# untitled.net
KiCad netlist of a schematic drawn in EAGLE
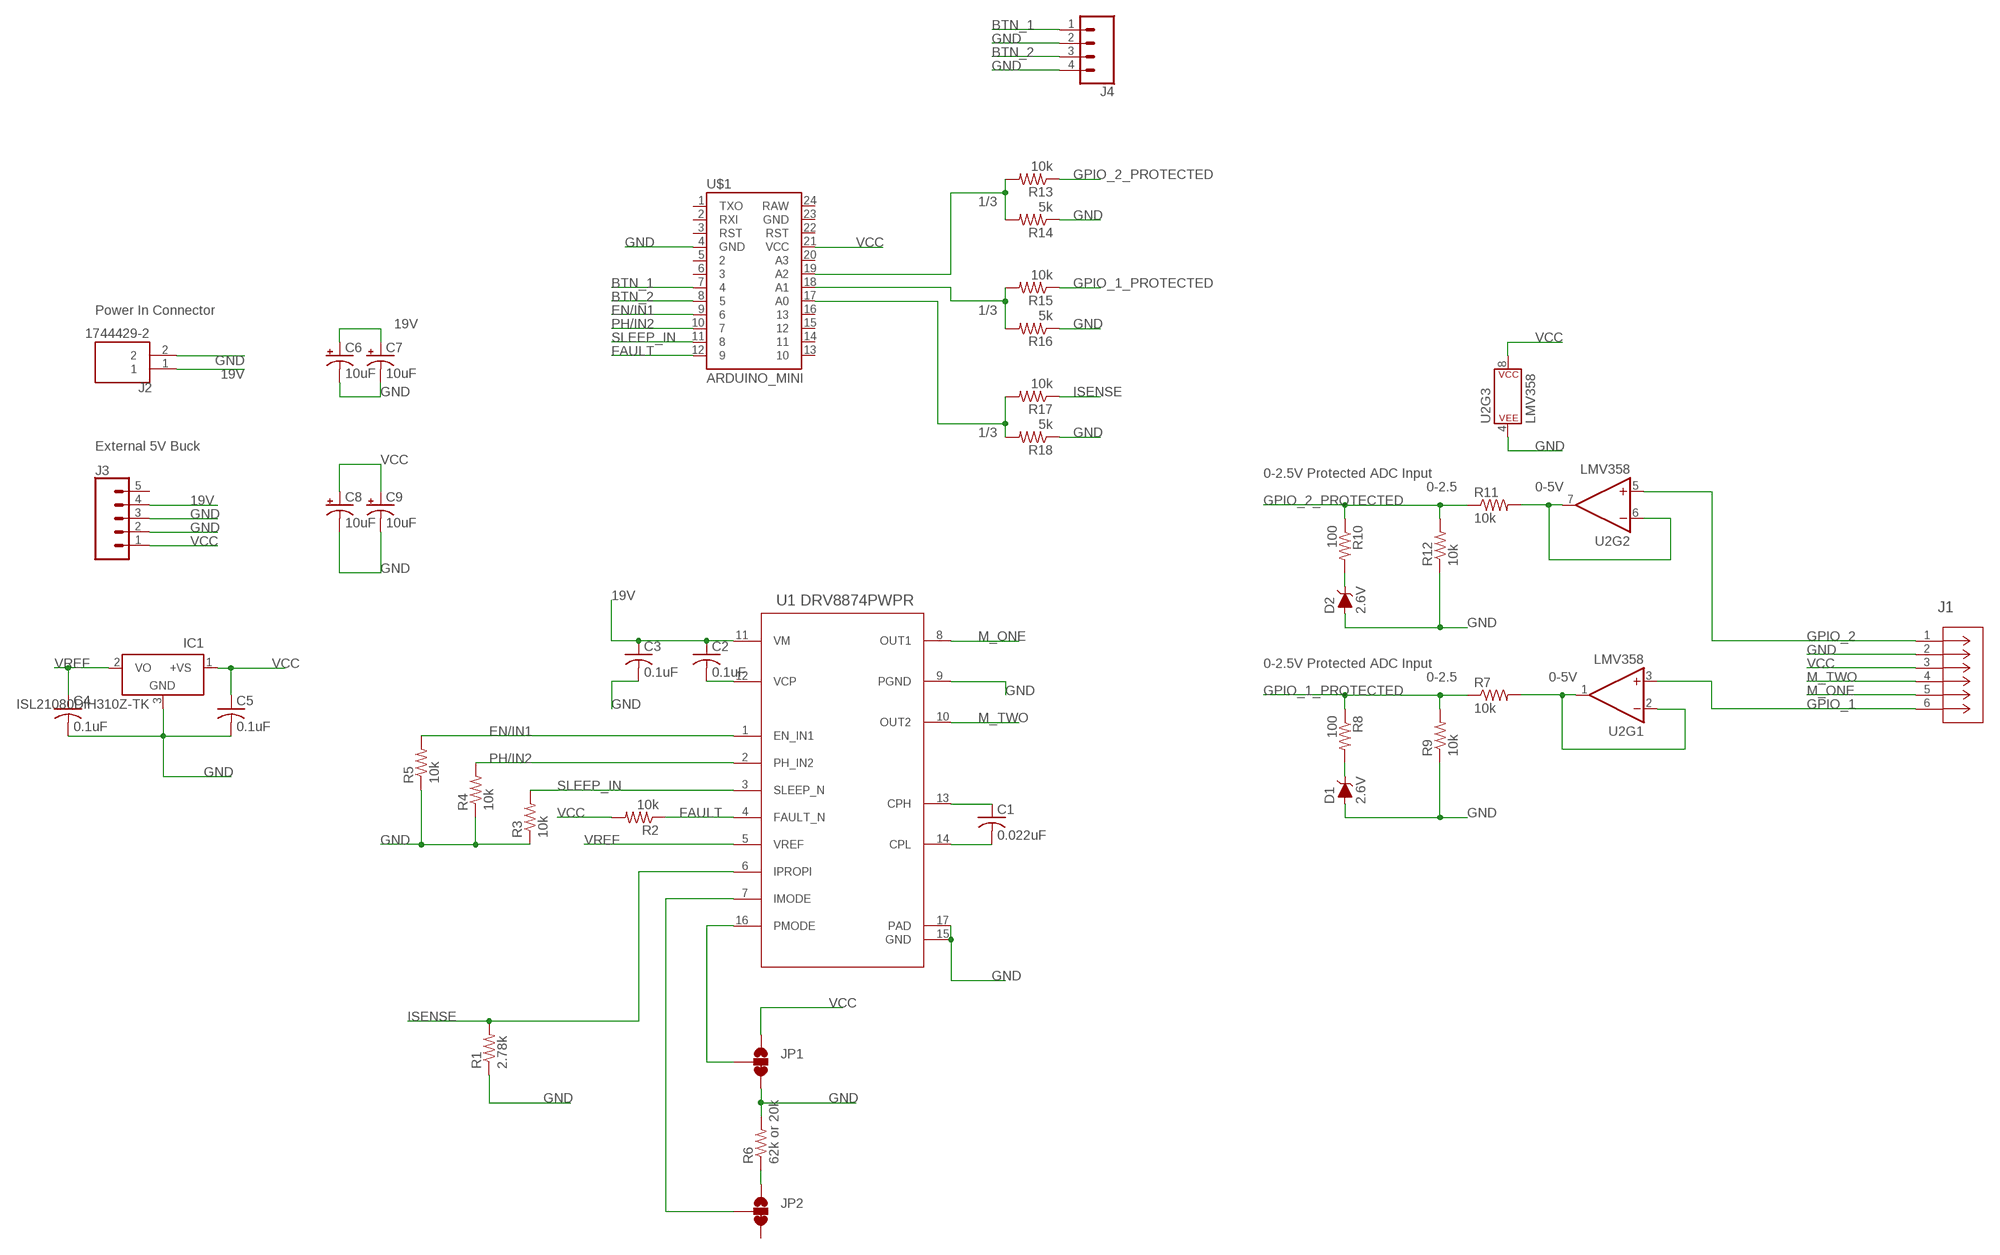
[diagram p0: schematic, sheet 1]

(export (version "E")
  (design (tool "Eeschema 10.0.6"))
  (components
    (comp (ref "C1")
      (value "0.022uF")
      (footprint "eagle-import:C0805K")
      (libsource (lib "eagle-import") (part "C-USC0805K"))
    )
    (comp (ref "C2")
      (value "0.1uF")
      (footprint "eagle-import:C0805K")
      (libsource (lib "eagle-import") (part "C-USC0805K"))
    )
    (comp (ref "C3")
      (value "0.1uF")
      (footprint "eagle-import:C0805K")
      (libsource (lib "eagle-import") (part "C-USC0805K"))
    )
    (comp (ref "C4")
      (value "0.1uF")
      (footprint "eagle-import:C0805K")
      (libsource (lib "eagle-import") (part "C-USC0805K"))
    )
    (comp (ref "C5")
      (value "0.1uF")
      (footprint "eagle-import:C0805K")
      (libsource (lib "eagle-import") (part "C-USC0805K"))
    )
    (comp (ref "C6")
      (value "10uF")
      (footprint "eagle-import:E2,5-6")
      (libsource (lib "eagle-import") (part "CPOL-USE2.5-6"))
    )
    (comp (ref "C7")
      (value "10uF")
      (footprint "eagle-import:E2,5-6")
      (libsource (lib "eagle-import") (part "CPOL-USE2.5-6"))
    )
    (comp (ref "C8")
      (value "10uF")
      (footprint "eagle-import:E2,5-6")
      (libsource (lib "eagle-import") (part "CPOL-USE2.5-6"))
    )
    (comp (ref "C9")
      (value "10uF")
      (footprint "eagle-import:E2,5-6")
      (libsource (lib "eagle-import") (part "CPOL-USE2.5-6"))
    )
    (comp (ref "D1")
      (value "2.6V")
      (footprint "eagle-import:SOD-323")
      (libsource (lib "eagle-import") (part "DIODE-ZENER-BZT52C3V6S"))
    )
    (comp (ref "D2")
      (value "2.6V")
      (footprint "eagle-import:SOD-323")
      (libsource (lib "eagle-import") (part "DIODE-ZENER-BZT52C3V6S"))
    )
    (comp (ref "IC1")
      (value "ISL21080DIH310Z-TK")
      (footprint "eagle-import:SOT23")
      (libsource (lib "eagle-import") (part "LM50"))
    )
    (comp (ref "J1")
      (value "39301060")
      (footprint "eagle-import:CON_39301060")
      (fields (field (name "COPYRIGHT") "Copyright (C) 2022 Ultra Librarian. All rights reserved."))
      (libsource (lib "eagle-import") (part "39301060"))
    )
    (comp (ref "J2")
      (value "1744429-2")
      (footprint "eagle-import:TE_1744429-2")
      (fields (field (name "MANUFACTURER") "TE"))
      (libsource (lib "eagle-import") (part "1744429-2"))
    )
    (comp (ref "J3")
      (value "CONN_05")
      (footprint "eagle-import:1X05")
      (libsource (lib "eagle-import") (part "CONN_05"))
    )
    (comp (ref "J4")
      (value "CONN_041X04_NO_SILK")
      (footprint "eagle-import:1X04_NO_SILK")
      (libsource (lib "eagle-import") (part "CONN_041X04_NO_SILK"))
    )
    (comp (ref "JP1")
      (value "JUMPER-SMT_3_1-NC_TRACE_SILK")
      (footprint "eagle-import:SMT-JUMPER_3_1-NC_TRACE_SILK")
      (libsource (lib "eagle-import") (part "JUMPER-SMT_3_1-NC_TRACE_SILK"))
    )
    (comp (ref "JP2")
      (value "JUMPER-SMT_3_1-NC_TRACE_SILK")
      (footprint "eagle-import:SMT-JUMPER_3_1-NC_TRACE_SILK")
      (libsource (lib "eagle-import") (part "JUMPER-SMT_3_1-NC_TRACE_SILK"))
    )
    (comp (ref "R1")
      (value "2.78k")
      (footprint "eagle-import:R0805")
      (libsource (lib "eagle-import") (part "R-US_R0805"))
    )
    (comp (ref "R2")
      (value "10k")
      (footprint "eagle-import:R0805")
      (libsource (lib "eagle-import") (part "R-US_R0805"))
    )
    (comp (ref "R3")
      (value "10k")
      (footprint "eagle-import:R0805")
      (libsource (lib "eagle-import") (part "R-US_R0805"))
    )
    (comp (ref "R4")
      (value "10k")
      (footprint "eagle-import:R0805")
      (libsource (lib "eagle-import") (part "R-US_R0805"))
    )
    (comp (ref "R5")
      (value "10k")
      (footprint "eagle-import:R0805")
      (libsource (lib "eagle-import") (part "R-US_R0805"))
    )
    (comp (ref "R6")
      (value "62k or 20k")
      (footprint "eagle-import:R0805")
      (libsource (lib "eagle-import") (part "R-US_R0805"))
    )
    (comp (ref "R7")
      (value "10k")
      (footprint "eagle-import:R0805")
      (libsource (lib "eagle-import") (part "R-US_R0805"))
    )
    (comp (ref "R8")
      (value "100")
      (footprint "eagle-import:R0805")
      (libsource (lib "eagle-import") (part "R-US_R0805"))
    )
    (comp (ref "R9")
      (value "10k")
      (footprint "eagle-import:R0805")
      (libsource (lib "eagle-import") (part "R-US_R0805"))
    )
    (comp (ref "R10")
      (value "100")
      (footprint "eagle-import:R0805")
      (libsource (lib "eagle-import") (part "R-US_R0805"))
    )
    (comp (ref "R11")
      (value "10k")
      (footprint "eagle-import:R0805")
      (libsource (lib "eagle-import") (part "R-US_R0805"))
    )
    (comp (ref "R12")
      (value "10k")
      (footprint "eagle-import:R0805")
      (libsource (lib "eagle-import") (part "R-US_R0805"))
    )
    (comp (ref "R13")
      (value "10k")
      (footprint "eagle-import:R0805")
      (libsource (lib "eagle-import") (part "R-US_R0805"))
    )
    (comp (ref "R14")
      (value "5k")
      (footprint "eagle-import:R0805")
      (libsource (lib "eagle-import") (part "R-US_R0805"))
    )
    (comp (ref "R15")
      (value "10k")
      (footprint "eagle-import:R0805")
      (libsource (lib "eagle-import") (part "R-US_R0805"))
    )
    (comp (ref "R16")
      (value "5k")
      (footprint "eagle-import:R0805")
      (libsource (lib "eagle-import") (part "R-US_R0805"))
    )
    (comp (ref "R17")
      (value "10k")
      (footprint "eagle-import:R0805")
      (libsource (lib "eagle-import") (part "R-US_R0805"))
    )
    (comp (ref "R18")
      (value "5k")
      (footprint "eagle-import:R0805")
      (libsource (lib "eagle-import") (part "R-US_R0805"))
    )
    (comp (ref "U$1")
      (value "ARDUINO_MINI")
      (footprint "eagle-import:ARDUINO_MINI")
      (libsource (lib "eagle-import") (part "ARDUINO_MINI"))
    )
    (comp (ref "U1")
      (value "DRV8874PWPR")
      (footprint "eagle-import:PWP0016J_N")
      (fields (field (name "COPYRIGHT") "Copyright (C) 2022 Ultra Librarian. All rights reserved."))
      (libsource (lib "eagle-import") (part "DRV8874PWPR"))
    )
    (comp (ref "U2")
      (value "LMV358")
      (footprint "eagle-import:SO08")
      (libsource (lib "eagle-import") (part "LMV358SOIC"))
    )
  )
  (nets
    (net (code "1") (name "/19V") (class "Default")
      (node (ref "C2") (pin "1") (pinfunction "1_1") (pintype "passive"))
      (node (ref "C3") (pin "1") (pinfunction "1_1") (pintype "passive"))
      (node (ref "C6") (pin "+") (pinfunction "+_+") (pintype "passive"))
      (node (ref "C7") (pin "+") (pinfunction "+_+") (pintype "passive"))
      (node (ref "J2") (pin "1") (pinfunction "1_1") (pintype "passive"))
      (node (ref "J3") (pin "4") (pinfunction "4_4") (pintype "passive"))
      (node (ref "U1") (pin "11") (pinfunction "VM_11") (pintype "power_in"))
    )
    (net (code "2") (name "/BTN_1") (class "Default")
      (node (ref "J4") (pin "1") (pinfunction "1_1") (pintype "passive"))
      (node (ref "U$1") (pin "7") (pinfunction "4_7") (pintype "bidirectional"))
    )
    (net (code "3") (name "/BTN_2") (class "Default")
      (node (ref "J4") (pin "3") (pinfunction "3_3") (pintype "passive"))
      (node (ref "U$1") (pin "8") (pinfunction "5_8") (pintype "bidirectional"))
    )
    (net (code "4") (name "/EN{slash}IN1") (class "Default")
      (node (ref "R5") (pin "2") (pinfunction "2_2") (pintype "passive"))
      (node (ref "U$1") (pin "9") (pinfunction "6_9") (pintype "bidirectional"))
      (node (ref "U1") (pin "1") (pinfunction "EN_IN1_1") (pintype "input"))
    )
    (net (code "5") (name "/FAULT") (class "Default")
      (node (ref "R2") (pin "1") (pinfunction "1_1") (pintype "passive"))
      (node (ref "U$1") (pin "12") (pinfunction "9_12") (pintype "bidirectional"))
      (node (ref "U1") (pin "4") (pinfunction "FAULT_N_4") (pintype "open_collector"))
    )
    (net (code "6") (name "/GND") (class "Default")
      (node (ref "C3") (pin "2") (pinfunction "2_2") (pintype "passive"))
      (node (ref "C4") (pin "2") (pinfunction "2_2") (pintype "passive"))
      (node (ref "C5") (pin "2") (pinfunction "2_2") (pintype "passive"))
      (node (ref "C6") (pin "-") (pinfunction "-_-") (pintype "passive"))
      (node (ref "C7") (pin "-") (pinfunction "-_-") (pintype "passive"))
      (node (ref "C8") (pin "-") (pinfunction "-_-") (pintype "passive"))
      (node (ref "C9") (pin "-") (pinfunction "-_-") (pintype "passive"))
      (node (ref "D1") (pin "A") (pinfunction "A_A") (pintype "passive"))
      (node (ref "D2") (pin "A") (pinfunction "A_A") (pintype "passive"))
      (node (ref "IC1") (pin "3") (pinfunction "GND_3") (pintype "power_in"))
      (node (ref "J1") (pin "2") (pinfunction "2_2") (pintype "passive"))
      (node (ref "J2") (pin "2") (pinfunction "2_2") (pintype "passive"))
      (node (ref "J3") (pin "2") (pinfunction "2_2") (pintype "passive"))
      (node (ref "J3") (pin "3") (pinfunction "3_3") (pintype "passive"))
      (node (ref "J4") (pin "2") (pinfunction "2_2") (pintype "passive"))
      (node (ref "J4") (pin "4") (pinfunction "4_4") (pintype "passive"))
      (node (ref "JP1") (pin "3") (pinfunction "3_3") (pintype "passive"))
      (node (ref "R1") (pin "1") (pinfunction "1_1") (pintype "passive"))
      (node (ref "R12") (pin "1") (pinfunction "1_1") (pintype "passive"))
      (node (ref "R14") (pin "1") (pinfunction "1_1") (pintype "passive"))
      (node (ref "R16") (pin "1") (pinfunction "1_1") (pintype "passive"))
      (node (ref "R18") (pin "1") (pinfunction "1_1") (pintype "passive"))
      (node (ref "R3") (pin "1") (pinfunction "1_1") (pintype "passive"))
      (node (ref "R4") (pin "1") (pinfunction "1_1") (pintype "passive"))
      (node (ref "R5") (pin "1") (pinfunction "1_1") (pintype "passive"))
      (node (ref "R6") (pin "2") (pinfunction "2_2") (pintype "passive"))
      (node (ref "R9") (pin "1") (pinfunction "1_1") (pintype "passive"))
      (node (ref "U$1") (pin "4") (pinfunction "GND_4") (pintype "bidirectional"))
      (node (ref "U1") (pin "15") (pinfunction "GND_15") (pintype "power_in"))
      (node (ref "U1") (pin "17") (pinfunction "PAD_17") (pintype "power_in"))
      (node (ref "U1") (pin "9") (pinfunction "PGND_9") (pintype "power_in"))
      (node (ref "U2") (pin "4") (pinfunction "P$V-_4") (pintype "bidirectional"))
    )
    (net (code "7") (name "/GPIO_1") (class "Default")
      (node (ref "J1") (pin "6") (pinfunction "6_6") (pintype "passive"))
      (node (ref "U2") (pin "3") (pinfunction "+IN_3") (pintype "input"))
    )
    (net (code "8") (name "/GPIO_1_PROTECTED") (class "Default")
      (node (ref "R15") (pin "1") (pinfunction "1_1") (pintype "passive"))
      (node (ref "R7") (pin "1") (pinfunction "1_1") (pintype "passive"))
      (node (ref "R8") (pin "1") (pinfunction "1_1") (pintype "passive"))
      (node (ref "R9") (pin "2") (pinfunction "2_2") (pintype "passive"))
    )
    (net (code "9") (name "/GPIO_2") (class "Default")
      (node (ref "J1") (pin "1") (pinfunction "1_1") (pintype "passive"))
      (node (ref "U2") (pin "5") (pinfunction "+IN_5") (pintype "input"))
    )
    (net (code "10") (name "/GPIO_2_PROTECTED") (class "Default")
      (node (ref "R10") (pin "1") (pinfunction "1_1") (pintype "passive"))
      (node (ref "R11") (pin "1") (pinfunction "1_1") (pintype "passive"))
      (node (ref "R12") (pin "2") (pinfunction "2_2") (pintype "passive"))
      (node (ref "R13") (pin "1") (pinfunction "1_1") (pintype "passive"))
    )
    (net (code "11") (name "/ISENSE") (class "Default")
      (node (ref "R1") (pin "2") (pinfunction "2_2") (pintype "passive"))
      (node (ref "R17") (pin "1") (pinfunction "1_1") (pintype "passive"))
      (node (ref "U1") (pin "6") (pinfunction "IPROPI_6") (pintype "output"))
    )
    (net (code "12") (name "/M_ONE") (class "Default")
      (node (ref "J1") (pin "5") (pinfunction "5_5") (pintype "passive"))
      (node (ref "U1") (pin "8") (pinfunction "OUT1_8") (pintype "output"))
    )
    (net (code "13") (name "/M_TWO") (class "Default")
      (node (ref "J1") (pin "4") (pinfunction "4_4") (pintype "passive"))
      (node (ref "U1") (pin "10") (pinfunction "OUT2_10") (pintype "output"))
    )
    (net (code "14") (name "/PH{slash}IN2") (class "Default")
      (node (ref "R4") (pin "2") (pinfunction "2_2") (pintype "passive"))
      (node (ref "U$1") (pin "10") (pinfunction "7_10") (pintype "bidirectional"))
      (node (ref "U1") (pin "2") (pinfunction "PH_IN2_2") (pintype "input"))
    )
    (net (code "15") (name "/SLEEP_IN") (class "Default")
      (node (ref "R3") (pin "2") (pinfunction "2_2") (pintype "passive"))
      (node (ref "U$1") (pin "11") (pinfunction "8_11") (pintype "bidirectional"))
      (node (ref "U1") (pin "3") (pinfunction "SLEEP_N_3") (pintype "input"))
    )
    (net (code "16") (name "/VCC") (class "Default")
      (node (ref "C5") (pin "1") (pinfunction "1_1") (pintype "passive"))
      (node (ref "C8") (pin "+") (pinfunction "+_+") (pintype "passive"))
      (node (ref "C9") (pin "+") (pinfunction "+_+") (pintype "passive"))
      (node (ref "IC1") (pin "1") (pinfunction "+VS_1") (pintype "input"))
      (node (ref "J1") (pin "3") (pinfunction "3_3") (pintype "passive"))
      (node (ref "J3") (pin "1") (pinfunction "1_1") (pintype "passive"))
      (node (ref "JP1") (pin "1") (pinfunction "1_1") (pintype "passive"))
      (node (ref "R2") (pin "2") (pinfunction "2_2") (pintype "passive"))
      (node (ref "U$1") (pin "21") (pinfunction "VCC_21") (pintype "bidirectional"))
      (node (ref "U2") (pin "8") (pinfunction "P$V+_8") (pintype "bidirectional"))
    )
    (net (code "17") (name "/VREF") (class "Default")
      (node (ref "C4") (pin "1") (pinfunction "1_1") (pintype "passive"))
      (node (ref "IC1") (pin "2") (pinfunction "VO_2") (pintype "input"))
      (node (ref "U1") (pin "5") (pinfunction "VREF_5") (pintype "power_in"))
    )
    (net (code "18") (name "Net-(D1-PadC)") (class "Default")
      (node (ref "D1") (pin "C") (pinfunction "C_C") (pintype "passive"))
      (node (ref "R8") (pin "2") (pinfunction "2_2") (pintype "passive"))
    )
    (net (code "19") (name "Net-(D2-PadC)") (class "Default")
      (node (ref "D2") (pin "C") (pinfunction "C_C") (pintype "passive"))
      (node (ref "R10") (pin "2") (pinfunction "2_2") (pintype "passive"))
    )
    (net (code "20") (name "Net-(JP2-Pad1)") (class "Default")
      (node (ref "JP2") (pin "1") (pinfunction "1_1") (pintype "passive"))
      (node (ref "R6") (pin "1") (pinfunction "1_1") (pintype "passive"))
    )
    (net (code "21") (name "Net-(U$1-A0)") (class "Default")
      (node (ref "R17") (pin "2") (pinfunction "2_2") (pintype "passive"))
      (node (ref "R18") (pin "2") (pinfunction "2_2") (pintype "passive"))
      (node (ref "U$1") (pin "17") (pinfunction "A0_17") (pintype "bidirectional"))
    )
    (net (code "22") (name "Net-(U$1-A1)") (class "Default")
      (node (ref "R15") (pin "2") (pinfunction "2_2") (pintype "passive"))
      (node (ref "R16") (pin "2") (pinfunction "2_2") (pintype "passive"))
      (node (ref "U$1") (pin "18") (pinfunction "A1_18") (pintype "bidirectional"))
    )
    (net (code "23") (name "Net-(U$1-A2)") (class "Default")
      (node (ref "R13") (pin "2") (pinfunction "2_2") (pintype "passive"))
      (node (ref "R14") (pin "2") (pinfunction "2_2") (pintype "passive"))
      (node (ref "U$1") (pin "19") (pinfunction "A2_19") (pintype "bidirectional"))
    )
    (net (code "24") (name "Net-(U1-CPH)") (class "Default")
      (node (ref "C1") (pin "1") (pinfunction "1_1") (pintype "passive"))
      (node (ref "U1") (pin "13") (pinfunction "CPH_13") (pintype "power_in"))
    )
    (net (code "25") (name "Net-(U1-CPL)") (class "Default")
      (node (ref "C1") (pin "2") (pinfunction "2_2") (pintype "passive"))
      (node (ref "U1") (pin "14") (pinfunction "CPL_14") (pintype "power_in"))
    )
    (net (code "26") (name "Net-(U1-IMODE)") (class "Default")
      (node (ref "JP2") (pin "2") (pinfunction "2_2") (pintype "passive"))
      (node (ref "U1") (pin "7") (pinfunction "IMODE_7") (pintype "input"))
    )
    (net (code "27") (name "Net-(U1-PMODE)") (class "Default")
      (node (ref "JP1") (pin "2") (pinfunction "2_2") (pintype "passive"))
      (node (ref "U1") (pin "16") (pinfunction "PMODE_16") (pintype "input"))
    )
    (net (code "28") (name "Net-(U1-VCP)") (class "Default")
      (node (ref "C2") (pin "2") (pinfunction "2_2") (pintype "passive"))
      (node (ref "U1") (pin "12") (pinfunction "VCP_12") (pintype "power_in"))
    )
    (net (code "29") (name "Net-(U2A--IN)") (class "Default")
      (node (ref "R7") (pin "2") (pinfunction "2_2") (pintype "passive"))
      (node (ref "U2") (pin "1") (pinfunction "OUT_1") (pintype "output"))
      (node (ref "U2") (pin "2") (pinfunction "-IN_2") (pintype "input"))
    )
    (net (code "30") (name "Net-(U2B--IN)") (class "Default")
      (node (ref "R11") (pin "2") (pinfunction "2_2") (pintype "passive"))
      (node (ref "U2") (pin "6") (pinfunction "-IN_6") (pintype "input"))
      (node (ref "U2") (pin "7") (pinfunction "OUT_7") (pintype "output"))
    )
    (net (code "31") (name "unconnected-(J3-Pad5)") (class "Default")
      (node (ref "J3") (pin "5") (pinfunction "5_5") (pintype "passive"))
    )
    (net (code "32") (name "unconnected-(JP2-Pad3)") (class "Default")
      (node (ref "JP2") (pin "3") (pinfunction "3_3") (pintype "passive"))
    )
    (net (code "33") (name "unconnected-(U$1-2-Pad5)") (class "Default")
      (node (ref "U$1") (pin "5") (pinfunction "2_5") (pintype "bidirectional"))
    )
    (net (code "34") (name "unconnected-(U$1-3-Pad6)") (class "Default")
      (node (ref "U$1") (pin "6") (pinfunction "3_6") (pintype "bidirectional"))
    )
    (net (code "35") (name "unconnected-(U$1-10-Pad13)") (class "Default")
      (node (ref "U$1") (pin "13") (pinfunction "10_13") (pintype "bidirectional"))
    )
    (net (code "36") (name "unconnected-(U$1-11-Pad14)") (class "Default")
      (node (ref "U$1") (pin "14") (pinfunction "11_14") (pintype "bidirectional"))
    )
    (net (code "37") (name "unconnected-(U$1-12-Pad15)") (class "Default")
      (node (ref "U$1") (pin "15") (pinfunction "12_15") (pintype "bidirectional"))
    )
    (net (code "38") (name "unconnected-(U$1-13-Pad16)") (class "Default")
      (node (ref "U$1") (pin "16") (pinfunction "13_16") (pintype "bidirectional"))
    )
    (net (code "39") (name "unconnected-(U$1-A3-Pad20)") (class "Default")
      (node (ref "U$1") (pin "20") (pinfunction "A3_20") (pintype "bidirectional"))
    )
    (net (code "40") (name "unconnected-(U$1-GND-Pad23)") (class "Default")
      (node (ref "U$1") (pin "23") (pinfunction "GND_23") (pintype "bidirectional"))
    )
    (net (code "41") (name "unconnected-(U$1-RAW-Pad24)") (class "Default")
      (node (ref "U$1") (pin "24") (pinfunction "RAW_24") (pintype "bidirectional"))
    )
    (net (code "42") (name "unconnected-(U$1-RST-Pad3)") (class "Default")
      (node (ref "U$1") (pin "3") (pinfunction "RST_3") (pintype "bidirectional"))
    )
    (net (code "43") (name "unconnected-(U$1-RST-Pad22)") (class "Default")
      (node (ref "U$1") (pin "22") (pinfunction "RST_22") (pintype "bidirectional"))
    )
    (net (code "44") (name "unconnected-(U$1-RXI-Pad2)") (class "Default")
      (node (ref "U$1") (pin "2") (pinfunction "RXI_2") (pintype "bidirectional"))
    )
    (net (code "45") (name "unconnected-(U$1-TXO-Pad1)") (class "Default")
      (node (ref "U$1") (pin "1") (pinfunction "TXO_1") (pintype "bidirectional"))
    )
  )
)
